# main.net
KiCad netlist of a schematic drawn in EAGLE
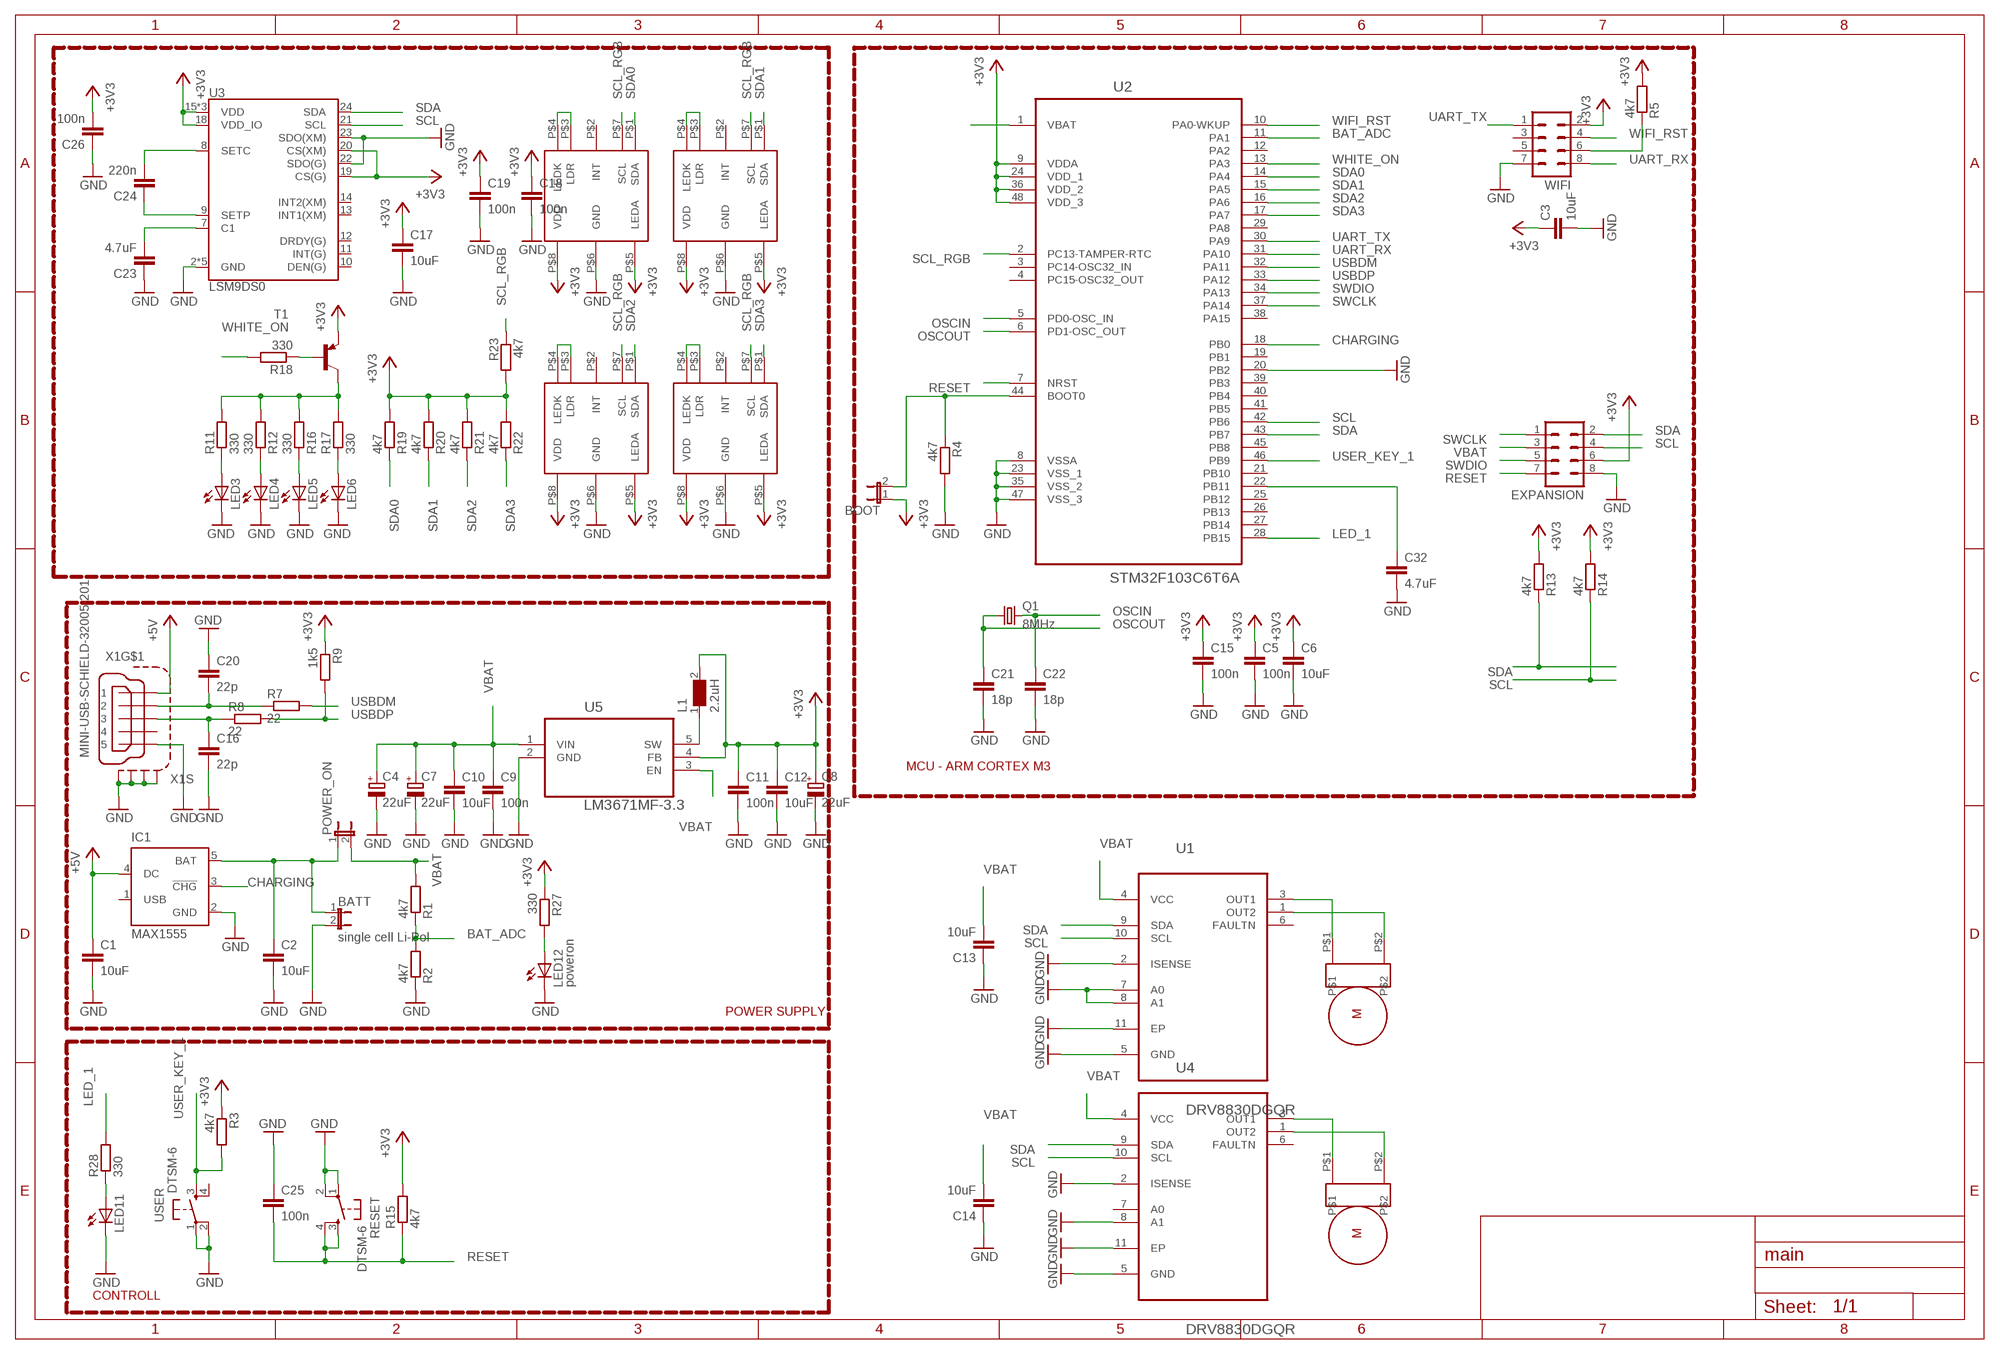
[diagram p0: schematic, sheet 1]

(export (version "E")
  (design (tool "Eeschema 10.0.6"))
  (components
    (comp (ref "BATT")
      (value "single cell Li-Pol")
      (footprint "eagle-import:JP1")
      (libsource (lib "eagle-import") (part "JP1E"))
    )
    (comp (ref "BOOT")
      (value "JP1E")
      (footprint "eagle-import:JP1")
      (libsource (lib "eagle-import") (part "JP1E"))
    )
    (comp (ref "C1")
      (value "10uF")
      (footprint "eagle-import:C0805")
      (libsource (lib "eagle-import") (part "C-EUC0805"))
    )
    (comp (ref "C2")
      (value "10uF")
      (footprint "eagle-import:C0805")
      (libsource (lib "eagle-import") (part "C-EUC0805"))
    )
    (comp (ref "C3")
      (value "10uF")
      (footprint "eagle-import:C0805")
      (libsource (lib "eagle-import") (part "C-EUC0805"))
    )
    (comp (ref "C4")
      (value "22uF")
      (footprint "eagle-import:153CLV-0505")
      (libsource (lib "eagle-import") (part "CPOL-EU153CLV-0505"))
    )
    (comp (ref "C5")
      (value "100n")
      (footprint "eagle-import:C0805")
      (libsource (lib "eagle-import") (part "C-EUC0805"))
    )
    (comp (ref "C6")
      (value "10uF")
      (footprint "eagle-import:C0805")
      (libsource (lib "eagle-import") (part "C-EUC0805"))
    )
    (comp (ref "C7")
      (value "22uF")
      (footprint "eagle-import:153CLV-0505")
      (libsource (lib "eagle-import") (part "CPOL-EU153CLV-0505"))
    )
    (comp (ref "C8")
      (value "22uF")
      (footprint "eagle-import:153CLV-0505")
      (libsource (lib "eagle-import") (part "CPOL-EU153CLV-0505"))
    )
    (comp (ref "C9")
      (value "100n")
      (footprint "eagle-import:C0805")
      (libsource (lib "eagle-import") (part "C-EUC0805"))
    )
    (comp (ref "C10")
      (value "10uF")
      (footprint "eagle-import:C0805")
      (libsource (lib "eagle-import") (part "C-EUC0805"))
    )
    (comp (ref "C11")
      (value "100n")
      (footprint "eagle-import:C0805")
      (libsource (lib "eagle-import") (part "C-EUC0805"))
    )
    (comp (ref "C12")
      (value "10uF")
      (footprint "eagle-import:C0805")
      (libsource (lib "eagle-import") (part "C-EUC0805"))
    )
    (comp (ref "C13")
      (value "10uF")
      (footprint "eagle-import:C0805")
      (libsource (lib "eagle-import") (part "C-EUC0805"))
    )
    (comp (ref "C14")
      (value "10uF")
      (footprint "eagle-import:C0805")
      (libsource (lib "eagle-import") (part "C-EUC0805"))
    )
    (comp (ref "C15")
      (value "100n")
      (footprint "eagle-import:C0805")
      (libsource (lib "eagle-import") (part "C-EUC0805"))
    )
    (comp (ref "C16")
      (value "22p")
      (footprint "eagle-import:C0805")
      (libsource (lib "eagle-import") (part "C-EUC0805"))
    )
    (comp (ref "C17")
      (value "10uF")
      (footprint "eagle-import:C0805")
      (libsource (lib "eagle-import") (part "C-EUC0805"))
    )
    (comp (ref "C18")
      (value "100n")
      (footprint "eagle-import:C0805")
      (libsource (lib "eagle-import") (part "C-EUC0805"))
    )
    (comp (ref "C19")
      (value "100n")
      (footprint "eagle-import:C0805")
      (libsource (lib "eagle-import") (part "C-EUC0805"))
    )
    (comp (ref "C20")
      (value "22p")
      (footprint "eagle-import:C0805")
      (libsource (lib "eagle-import") (part "C-EUC0805"))
    )
    (comp (ref "C21")
      (value "18p")
      (footprint "eagle-import:C0805")
      (libsource (lib "eagle-import") (part "C-EUC0805"))
    )
    (comp (ref "C22")
      (value "18p")
      (footprint "eagle-import:C0805")
      (libsource (lib "eagle-import") (part "C-EUC0805"))
    )
    (comp (ref "C23")
      (value "4.7uF")
      (footprint "eagle-import:C0805")
      (libsource (lib "eagle-import") (part "C-EUC0805"))
    )
    (comp (ref "C24")
      (value "220n")
      (footprint "eagle-import:C0805")
      (libsource (lib "eagle-import") (part "C-EUC0805"))
    )
    (comp (ref "C25")
      (value "100n")
      (footprint "eagle-import:C0805")
      (libsource (lib "eagle-import") (part "C-EUC0805"))
    )
    (comp (ref "C26")
      (value "100n")
      (footprint "eagle-import:C0805")
      (libsource (lib "eagle-import") (part "C-EUC0805"))
    )
    (comp (ref "C32")
      (value "4.7uF")
      (footprint "eagle-import:C0805")
      (libsource (lib "eagle-import") (part "C-EUC0805"))
    )
    (comp (ref "EXPANSION")
      (value "MA04-2")
      (footprint "eagle-import:MA04-2")
      (libsource (lib "eagle-import") (part "MA04-2"))
    )
    (comp (ref "IC1")
      (value "MAX1555")
      (footprint "eagle-import:SOT23-5L")
      (fields (field (name "MF") "MAXIM") (field (name "MPN") "MAX1555EZK+T"))
      (libsource (lib "eagle-import") (part "MAX1555"))
    )
    (comp (ref "L1")
      (value "2.2uH")
      (footprint "eagle-import:WE-LQ_M")
      (fields (field (name "MPN") "744032002 "))
      (libsource (lib "eagle-import") (part "WE-LQ_M-744032002"))
    )
    (comp (ref "LED3")
      (value "LEDCHIPLED_1206")
      (footprint "eagle-import:CHIPLED_1206")
      (libsource (lib "eagle-import") (part "LEDCHIPLED_1206"))
    )
    (comp (ref "LED4")
      (value "LEDCHIPLED_1206")
      (footprint "eagle-import:CHIPLED_1206")
      (libsource (lib "eagle-import") (part "LEDCHIPLED_1206"))
    )
    (comp (ref "LED5")
      (value "LEDCHIPLED_1206")
      (footprint "eagle-import:CHIPLED_1206")
      (libsource (lib "eagle-import") (part "LEDCHIPLED_1206"))
    )
    (comp (ref "LED6")
      (value "LEDCHIPLED_1206")
      (footprint "eagle-import:CHIPLED_1206")
      (libsource (lib "eagle-import") (part "LEDCHIPLED_1206"))
    )
    (comp (ref "LED11")
      (value "LEDCHIPLED_1206")
      (footprint "eagle-import:CHIPLED_1206")
      (libsource (lib "eagle-import") (part "LEDCHIPLED_1206"))
    )
    (comp (ref "LED12")
      (value "poweron")
      (footprint "eagle-import:CHIPLED_1206")
      (libsource (lib "eagle-import") (part "LEDCHIPLED_1206"))
    )
    (comp (ref "POWER_ON")
      (value "JP1E")
      (footprint "eagle-import:JP1")
      (libsource (lib "eagle-import") (part "JP1E"))
    )
    (comp (ref "Q1")
      (value "8MHz")
      (footprint "eagle-import:CTS406")
      (libsource (lib "eagle-import") (part "CRYSTALCTS406"))
    )
    (comp (ref "R1")
      (value "4k7")
      (footprint "eagle-import:M0805")
      (libsource (lib "eagle-import") (part "R-EU_M0805"))
    )
    (comp (ref "R2")
      (value "4k7")
      (footprint "eagle-import:M0805")
      (libsource (lib "eagle-import") (part "R-EU_M0805"))
    )
    (comp (ref "R3")
      (value "4k7")
      (footprint "eagle-import:M0805")
      (libsource (lib "eagle-import") (part "R-EU_M0805"))
    )
    (comp (ref "R4")
      (value "4k7")
      (footprint "eagle-import:M0805")
      (libsource (lib "eagle-import") (part "R-EU_M0805"))
    )
    (comp (ref "R5")
      (value "4k7")
      (footprint "eagle-import:M0805")
      (libsource (lib "eagle-import") (part "R-EU_M0805"))
    )
    (comp (ref "R7")
      (value "22")
      (footprint "eagle-import:M0805")
      (libsource (lib "eagle-import") (part "R-EU_M0805"))
    )
    (comp (ref "R8")
      (value "22")
      (footprint "eagle-import:M0805")
      (libsource (lib "eagle-import") (part "R-EU_M0805"))
    )
    (comp (ref "R9")
      (value "1k5")
      (footprint "eagle-import:M0805")
      (libsource (lib "eagle-import") (part "R-EU_M0805"))
    )
    (comp (ref "R11")
      (value "330")
      (footprint "eagle-import:M0805")
      (libsource (lib "eagle-import") (part "R-EU_M0805"))
    )
    (comp (ref "R12")
      (value "330")
      (footprint "eagle-import:M0805")
      (libsource (lib "eagle-import") (part "R-EU_M0805"))
    )
    (comp (ref "R13")
      (value "4k7")
      (footprint "eagle-import:M0805")
      (libsource (lib "eagle-import") (part "R-EU_M0805"))
    )
    (comp (ref "R14")
      (value "4k7")
      (footprint "eagle-import:M0805")
      (libsource (lib "eagle-import") (part "R-EU_M0805"))
    )
    (comp (ref "R15")
      (value "4k7")
      (footprint "eagle-import:M0805")
      (libsource (lib "eagle-import") (part "R-EU_M0805"))
    )
    (comp (ref "R16")
      (value "330")
      (footprint "eagle-import:M0805")
      (libsource (lib "eagle-import") (part "R-EU_M0805"))
    )
    (comp (ref "R17")
      (value "330")
      (footprint "eagle-import:M0805")
      (libsource (lib "eagle-import") (part "R-EU_M0805"))
    )
    (comp (ref "R18")
      (value "330")
      (footprint "eagle-import:M0805")
      (libsource (lib "eagle-import") (part "R-EU_M0805"))
    )
    (comp (ref "R19")
      (value "4k7")
      (footprint "eagle-import:M0805")
      (libsource (lib "eagle-import") (part "R-EU_M0805"))
    )
    (comp (ref "R20")
      (value "4k7")
      (footprint "eagle-import:M0805")
      (libsource (lib "eagle-import") (part "R-EU_M0805"))
    )
    (comp (ref "R21")
      (value "4k7")
      (footprint "eagle-import:M0805")
      (libsource (lib "eagle-import") (part "R-EU_M0805"))
    )
    (comp (ref "R22")
      (value "4k7")
      (footprint "eagle-import:M0805")
      (libsource (lib "eagle-import") (part "R-EU_M0805"))
    )
    (comp (ref "R23")
      (value "4k7")
      (footprint "eagle-import:M0805")
      (libsource (lib "eagle-import") (part "R-EU_M0805"))
    )
    (comp (ref "R27")
      (value "330")
      (footprint "eagle-import:M0805")
      (libsource (lib "eagle-import") (part "R-EU_M0805"))
    )
    (comp (ref "R28")
      (value "330")
      (footprint "eagle-import:M0805")
      (libsource (lib "eagle-import") (part "R-EU_M0805"))
    )
    (comp (ref "RESET")
      (value "DTSM-6")
      (footprint "eagle-import:DTSM-6")
      (libsource (lib "eagle-import") (part "DTSM-6"))
    )
    (comp (ref "T1")
      (value "BC857A-PNP-SOT23-BEC")
      (footprint "eagle-import:SOT23-BEC")
      (libsource (lib "eagle-import") (part "-PNP-SOT23-BECBC857A"))
    )
    (comp (ref "U$1")
      (value "APDS9950")
      (footprint "eagle-import:APDS9950")
      (libsource (lib "eagle-import") (part "APDS9950"))
    )
    (comp (ref "U$2")
      (value "APDS9950")
      (footprint "eagle-import:APDS9950")
      (libsource (lib "eagle-import") (part "APDS9950"))
    )
    (comp (ref "U$3")
      (value "APDS9950")
      (footprint "eagle-import:APDS9950")
      (libsource (lib "eagle-import") (part "APDS9950"))
    )
    (comp (ref "U$4")
      (value "APDS9950")
      (footprint "eagle-import:APDS9950")
      (libsource (lib "eagle-import") (part "APDS9950"))
    )
    (comp (ref "U$5")
      (value "MICRO_METAL_GEAR_MOTOR")
      (footprint "eagle-import:MICRO_METAL_GEAR_MOTOR")
      (libsource (lib "eagle-import") (part "MICRO_METAL_GEAR_MOTOR"))
    )
    (comp (ref "U$6")
      (value "MICRO_METAL_GEAR_MOTOR")
      (footprint "eagle-import:MICRO_METAL_GEAR_MOTOR")
      (libsource (lib "eagle-import") (part "MICRO_METAL_GEAR_MOTOR"))
    )
    (comp (ref "U1")
      (value "DRV8830DGQR")
      (footprint "eagle-import:SOP65P640X110-15N")
      (libsource (lib "eagle-import") (part "DRV8830DGQR"))
    )
    (comp (ref "U2")
      (value "STM32F103C6T6A")
      (footprint "eagle-import:QFP50P900X900X160-48N")
      (libsource (lib "eagle-import") (part "STM32F103C6T6A"))
    )
    (comp (ref "U3")
      (value "LSM9DS0")
      (footprint "eagle-import:LGA-24")
      (libsource (lib "eagle-import") (part "LSM9DS0"))
    )
    (comp (ref "U4")
      (value "DRV8830DGQR")
      (footprint "eagle-import:SOP65P640X110-15N")
      (libsource (lib "eagle-import") (part "DRV8830DGQR"))
    )
    (comp (ref "U5")
      (value "LM3671MF-3.3")
      (footprint "eagle-import:SOT95P284X122-5N")
      (libsource (lib "eagle-import") (part "LM3671MF-3.3"))
    )
    (comp (ref "USER")
      (value "DTSM-6")
      (footprint "eagle-import:DTSM-6")
      (libsource (lib "eagle-import") (part "DTSM-6"))
    )
    (comp (ref "WIFI")
      (value "MA04-2")
      (footprint "eagle-import:MA04-2")
      (libsource (lib "eagle-import") (part "MA04-2"))
    )
    (comp (ref "X1")
      (value "MINI-USB-SCHIELD-32005-201")
      (footprint "eagle-import:32005-201")
      (libsource (lib "eagle-import") (part "MINI-USB-SCHIELD-32005-201"))
    )
  )
  (nets
    (net (code "1") (name "+3V3") (class "Default")
      (node (ref "BOOT") (pin "1") (pinfunction "1_1") (pintype "passive"))
      (node (ref "C11") (pin "1") (pinfunction "1_1") (pintype "passive"))
      (node (ref "C12") (pin "1") (pinfunction "1_1") (pintype "passive"))
      (node (ref "C15") (pin "1") (pinfunction "1_1") (pintype "passive"))
      (node (ref "C17") (pin "1") (pinfunction "1_1") (pintype "passive"))
      (node (ref "C18") (pin "1") (pinfunction "1_1") (pintype "passive"))
      (node (ref "C19") (pin "1") (pinfunction "1_1") (pintype "passive"))
      (node (ref "C26") (pin "2") (pinfunction "2_2") (pintype "passive"))
      (node (ref "C3") (pin "1") (pinfunction "1_1") (pintype "passive"))
      (node (ref "C5") (pin "1") (pinfunction "1_1") (pintype "passive"))
      (node (ref "C6") (pin "1") (pinfunction "1_1") (pintype "passive"))
      (node (ref "C8") (pin "+") (pinfunction "+_+") (pintype "passive"))
      (node (ref "EXPANSION") (pin "6") (pinfunction "6_6") (pintype "passive"))
      (node (ref "L1") (pin "2") (pinfunction "2_2") (pintype "passive"))
      (node (ref "R13") (pin "2") (pinfunction "2_2") (pintype "passive"))
      (node (ref "R14") (pin "2") (pinfunction "2_2") (pintype "passive"))
      (node (ref "R15") (pin "2") (pinfunction "2_2") (pintype "passive"))
      (node (ref "R19") (pin "2") (pinfunction "2_2") (pintype "passive"))
      (node (ref "R20") (pin "2") (pinfunction "2_2") (pintype "passive"))
      (node (ref "R21") (pin "2") (pinfunction "2_2") (pintype "passive"))
      (node (ref "R22") (pin "2") (pinfunction "2_2") (pintype "passive"))
      (node (ref "R23") (pin "2") (pinfunction "2_2") (pintype "passive"))
      (node (ref "R27") (pin "1") (pinfunction "1_1") (pintype "passive"))
      (node (ref "R3") (pin "1") (pinfunction "1_1") (pintype "passive"))
      (node (ref "R5") (pin "2") (pinfunction "2_2") (pintype "passive"))
      (node (ref "R9") (pin "1") (pinfunction "1_1") (pintype "passive"))
      (node (ref "T1") (pin "E") (pinfunction "E_E") (pintype "passive"))
      (node (ref "U$1") (pin "P$5") (pinfunction "LEDA_P$5") (pintype "bidirectional"))
      (node (ref "U$1") (pin "P$8") (pinfunction "VDD_P$8") (pintype "bidirectional"))
      (node (ref "U$2") (pin "P$5") (pinfunction "LEDA_P$5") (pintype "bidirectional"))
      (node (ref "U$2") (pin "P$8") (pinfunction "VDD_P$8") (pintype "bidirectional"))
      (node (ref "U$3") (pin "P$5") (pinfunction "LEDA_P$5") (pintype "bidirectional"))
      (node (ref "U$3") (pin "P$8") (pinfunction "VDD_P$8") (pintype "bidirectional"))
      (node (ref "U$4") (pin "P$5") (pinfunction "LEDA_P$5") (pintype "bidirectional"))
      (node (ref "U$4") (pin "P$8") (pinfunction "VDD_P$8") (pintype "bidirectional"))
      (node (ref "U2") (pin "24") (pinfunction "VDD_1_24") (pintype "power_in"))
      (node (ref "U2") (pin "36") (pinfunction "VDD_2_36") (pintype "power_in"))
      (node (ref "U2") (pin "48") (pinfunction "VDD_3_48") (pintype "power_in"))
      (node (ref "U2") (pin "9") (pinfunction "VDDA_9") (pintype "power_in"))
      (node (ref "U3") (pin "15") (pinfunction "VDD_15") (pintype "bidirectional"))
      (node (ref "U3") (pin "16") (pinfunction "VDD_16") (pintype "bidirectional"))
      (node (ref "U3") (pin "17") (pinfunction "VDD_17") (pintype "bidirectional"))
      (node (ref "U3") (pin "18") (pinfunction "VDD_IO_18") (pintype "bidirectional"))
      (node (ref "U3") (pin "19") (pinfunction "CS(G)_19") (pintype "bidirectional"))
      (node (ref "U3") (pin "20") (pinfunction "CS(XM)_20") (pintype "bidirectional"))
      (node (ref "U5") (pin "4") (pinfunction "FB_4") (pintype "passive"))
      (node (ref "WIFI") (pin "2") (pinfunction "2_2") (pintype "passive"))
    )
    (net (code "2") (name "+5V") (class "Default")
      (node (ref "C1") (pin "1") (pinfunction "1_1") (pintype "passive"))
      (node (ref "IC1") (pin "4") (pinfunction "DC_4") (pintype "input"))
      (node (ref "X1") (pin "1") (pinfunction "1_1") (pintype "passive"))
    )
    (net (code "3") (name "/BAT_ADC") (class "Default")
      (node (ref "R1") (pin "1") (pinfunction "1_1") (pintype "passive"))
      (node (ref "R2") (pin "2") (pinfunction "2_2") (pintype "passive"))
      (node (ref "U2") (pin "11") (pinfunction "PA1_11") (pintype "bidirectional"))
    )
    (net (code "4") (name "/CHARGING") (class "Default")
      (node (ref "IC1") (pin "3") (pinfunction "~{CHG}_3") (pintype "output"))
      (node (ref "U2") (pin "18") (pinfunction "PB0_18") (pintype "bidirectional"))
    )
    (net (code "5") (name "/LED_1") (class "Default")
      (node (ref "R28") (pin "2") (pinfunction "2_2") (pintype "passive"))
      (node (ref "U2") (pin "28") (pinfunction "PB15_28") (pintype "bidirectional"))
    )
    (net (code "6") (name "/OSCIN") (class "Default")
      (node (ref "C22") (pin "1") (pinfunction "1_1") (pintype "passive"))
      (node (ref "Q1") (pin "3") (pinfunction "2_3") (pintype "passive"))
      (node (ref "U2") (pin "5") (pinfunction "PD0-OSC_IN_5") (pintype "bidirectional"))
    )
    (net (code "7") (name "/OSCOUT") (class "Default")
      (node (ref "C21") (pin "1") (pinfunction "1_1") (pintype "passive"))
      (node (ref "Q1") (pin "1") (pinfunction "1_1") (pintype "passive"))
      (node (ref "U2") (pin "6") (pinfunction "PD1-OSC_OUT_6") (pintype "bidirectional"))
    )
    (net (code "8") (name "/RESET") (class "Default")
      (node (ref "C25") (pin "2") (pinfunction "2_2") (pintype "passive"))
      (node (ref "EXPANSION") (pin "7") (pinfunction "7_7") (pintype "passive"))
      (node (ref "R15") (pin "1") (pinfunction "1_1") (pintype "passive"))
      (node (ref "RESET") (pin "3") (pinfunction "3_3") (pintype "passive"))
      (node (ref "RESET") (pin "4") (pinfunction "4_4") (pintype "passive"))
      (node (ref "U2") (pin "7") (pinfunction "NRST_7") (pintype "bidirectional"))
    )
    (net (code "9") (name "/SCL") (class "Default")
      (node (ref "EXPANSION") (pin "4") (pinfunction "4_4") (pintype "passive"))
      (node (ref "R14") (pin "1") (pinfunction "1_1") (pintype "passive"))
      (node (ref "U1") (pin "10") (pinfunction "SCL_10") (pintype "input"))
      (node (ref "U2") (pin "42") (pinfunction "PB6_42") (pintype "bidirectional"))
      (node (ref "U3") (pin "21") (pinfunction "SCL_21") (pintype "bidirectional"))
      (node (ref "U4") (pin "10") (pinfunction "SCL_10") (pintype "input"))
    )
    (net (code "10") (name "/SCL_RGB") (class "Default")
      (node (ref "R23") (pin "1") (pinfunction "1_1") (pintype "passive"))
      (node (ref "U$1") (pin "P$7") (pinfunction "SCL_P$7") (pintype "bidirectional"))
      (node (ref "U$2") (pin "P$7") (pinfunction "SCL_P$7") (pintype "bidirectional"))
      (node (ref "U$3") (pin "P$7") (pinfunction "SCL_P$7") (pintype "bidirectional"))
      (node (ref "U$4") (pin "P$7") (pinfunction "SCL_P$7") (pintype "bidirectional"))
      (node (ref "U2") (pin "2") (pinfunction "PC13-TAMPER-RTC_2") (pintype "bidirectional"))
    )
    (net (code "11") (name "/SDA") (class "Default")
      (node (ref "EXPANSION") (pin "2") (pinfunction "2_2") (pintype "passive"))
      (node (ref "R13") (pin "1") (pinfunction "1_1") (pintype "passive"))
      (node (ref "U1") (pin "9") (pinfunction "SDA_9") (pintype "bidirectional"))
      (node (ref "U2") (pin "43") (pinfunction "PB7_43") (pintype "bidirectional"))
      (node (ref "U3") (pin "24") (pinfunction "SDA_24") (pintype "bidirectional"))
      (node (ref "U4") (pin "9") (pinfunction "SDA_9") (pintype "bidirectional"))
    )
    (net (code "12") (name "/SDA0") (class "Default")
      (node (ref "R19") (pin "1") (pinfunction "1_1") (pintype "passive"))
      (node (ref "U$1") (pin "P$1") (pinfunction "SDA_P$1") (pintype "bidirectional"))
      (node (ref "U2") (pin "14") (pinfunction "PA4_14") (pintype "bidirectional"))
    )
    (net (code "13") (name "/SDA1") (class "Default")
      (node (ref "R20") (pin "1") (pinfunction "1_1") (pintype "passive"))
      (node (ref "U$2") (pin "P$1") (pinfunction "SDA_P$1") (pintype "bidirectional"))
      (node (ref "U2") (pin "15") (pinfunction "PA5_15") (pintype "bidirectional"))
    )
    (net (code "14") (name "/SDA2") (class "Default")
      (node (ref "R21") (pin "1") (pinfunction "1_1") (pintype "passive"))
      (node (ref "U$3") (pin "P$1") (pinfunction "SDA_P$1") (pintype "bidirectional"))
      (node (ref "U2") (pin "16") (pinfunction "PA6_16") (pintype "bidirectional"))
    )
    (net (code "15") (name "/SDA3") (class "Default")
      (node (ref "R22") (pin "1") (pinfunction "1_1") (pintype "passive"))
      (node (ref "U$4") (pin "P$1") (pinfunction "SDA_P$1") (pintype "bidirectional"))
      (node (ref "U2") (pin "17") (pinfunction "PA7_17") (pintype "bidirectional"))
    )
    (net (code "16") (name "/SWCLK") (class "Default")
      (node (ref "EXPANSION") (pin "1") (pinfunction "1_1") (pintype "passive"))
      (node (ref "U2") (pin "37") (pinfunction "PA14_37") (pintype "bidirectional"))
    )
    (net (code "17") (name "/SWDIO") (class "Default")
      (node (ref "EXPANSION") (pin "5") (pinfunction "5_5") (pintype "passive"))
      (node (ref "U2") (pin "34") (pinfunction "PA13_34") (pintype "bidirectional"))
    )
    (net (code "18") (name "/UART_RX") (class "Default")
      (node (ref "U2") (pin "31") (pinfunction "PA10_31") (pintype "bidirectional"))
      (node (ref "WIFI") (pin "8") (pinfunction "8_8") (pintype "passive"))
    )
    (net (code "19") (name "/UART_TX") (class "Default")
      (node (ref "U2") (pin "30") (pinfunction "PA9_30") (pintype "bidirectional"))
      (node (ref "WIFI") (pin "1") (pinfunction "1_1") (pintype "passive"))
    )
    (net (code "20") (name "/USBDM") (class "Default")
      (node (ref "R7") (pin "2") (pinfunction "2_2") (pintype "passive"))
      (node (ref "U2") (pin "32") (pinfunction "PA11_32") (pintype "bidirectional"))
    )
    (net (code "21") (name "/USBDP") (class "Default")
      (node (ref "R8") (pin "2") (pinfunction "2_2") (pintype "passive"))
      (node (ref "R9") (pin "2") (pinfunction "2_2") (pintype "passive"))
      (node (ref "U2") (pin "33") (pinfunction "PA12_33") (pintype "bidirectional"))
    )
    (net (code "22") (name "/USER_KEY_1") (class "Default")
      (node (ref "R3") (pin "2") (pinfunction "2_2") (pintype "passive"))
      (node (ref "U2") (pin "46") (pinfunction "PB9_46") (pintype "bidirectional"))
      (node (ref "USER") (pin "3") (pinfunction "3_3") (pintype "passive"))
    )
    (net (code "23") (name "/VBAT") (class "Default")
      (node (ref "C10") (pin "1") (pinfunction "1_1") (pintype "passive"))
      (node (ref "C13") (pin "2") (pinfunction "2_2") (pintype "passive"))
      (node (ref "C14") (pin "2") (pinfunction "2_2") (pintype "passive"))
      (node (ref "C4") (pin "+") (pinfunction "+_+") (pintype "passive"))
      (node (ref "C7") (pin "+") (pinfunction "+_+") (pintype "passive"))
      (node (ref "C9") (pin "1") (pinfunction "1_1") (pintype "passive"))
      (node (ref "EXPANSION") (pin "3") (pinfunction "3_3") (pintype "passive"))
      (node (ref "POWER_ON") (pin "2") (pinfunction "2_2") (pintype "passive"))
      (node (ref "R1") (pin "2") (pinfunction "2_2") (pintype "passive"))
      (node (ref "U1") (pin "4") (pinfunction "VCC_4") (pintype "power_in"))
      (node (ref "U4") (pin "4") (pinfunction "VCC_4") (pintype "power_in"))
      (node (ref "U5") (pin "1") (pinfunction "VIN_1") (pintype "input"))
      (node (ref "U5") (pin "3") (pinfunction "EN_3") (pintype "passive"))
    )
    (net (code "24") (name "/WHITE_ON") (class "Default")
      (node (ref "R18") (pin "2") (pinfunction "2_2") (pintype "passive"))
      (node (ref "U2") (pin "13") (pinfunction "PA3_13") (pintype "bidirectional"))
    )
    (net (code "25") (name "/WIFI_RST") (class "Default")
      (node (ref "U2") (pin "10") (pinfunction "PA0-WKUP_10") (pintype "bidirectional"))
      (node (ref "WIFI") (pin "4") (pinfunction "4_4") (pintype "passive"))
    )
    (net (code "26") (name "GND") (class "Default")
      (node (ref "BATT") (pin "2") (pinfunction "2_2") (pintype "passive"))
      (node (ref "C1") (pin "2") (pinfunction "2_2") (pintype "passive"))
      (node (ref "C10") (pin "2") (pinfunction "2_2") (pintype "passive"))
      (node (ref "C11") (pin "2") (pinfunction "2_2") (pintype "passive"))
      (node (ref "C12") (pin "2") (pinfunction "2_2") (pintype "passive"))
      (node (ref "C13") (pin "1") (pinfunction "1_1") (pintype "passive"))
      (node (ref "C14") (pin "1") (pinfunction "1_1") (pintype "passive"))
      (node (ref "C15") (pin "2") (pinfunction "2_2") (pintype "passive"))
      (node (ref "C16") (pin "2") (pinfunction "2_2") (pintype "passive"))
      (node (ref "C17") (pin "2") (pinfunction "2_2") (pintype "passive"))
      (node (ref "C18") (pin "2") (pinfunction "2_2") (pintype "passive"))
      (node (ref "C19") (pin "2") (pinfunction "2_2") (pintype "passive"))
      (node (ref "C2") (pin "2") (pinfunction "2_2") (pintype "passive"))
      (node (ref "C20") (pin "1") (pinfunction "1_1") (pintype "passive"))
      (node (ref "C21") (pin "2") (pinfunction "2_2") (pintype "passive"))
      (node (ref "C22") (pin "2") (pinfunction "2_2") (pintype "passive"))
      (node (ref "C23") (pin "1") (pinfunction "1_1") (pintype "passive"))
      (node (ref "C25") (pin "1") (pinfunction "1_1") (pintype "passive"))
      (node (ref "C26") (pin "1") (pinfunction "1_1") (pintype "passive"))
      (node (ref "C3") (pin "2") (pinfunction "2_2") (pintype "passive"))
      (node (ref "C32") (pin "2") (pinfunction "2_2") (pintype "passive"))
      (node (ref "C4") (pin "-") (pinfunction "-_-") (pintype "passive"))
      (node (ref "C5") (pin "2") (pinfunction "2_2") (pintype "passive"))
      (node (ref "C6") (pin "2") (pinfunction "2_2") (pintype "passive"))
      (node (ref "C7") (pin "-") (pinfunction "-_-") (pintype "passive"))
      (node (ref "C8") (pin "-") (pinfunction "-_-") (pintype "passive"))
      (node (ref "C9") (pin "2") (pinfunction "2_2") (pintype "passive"))
      (node (ref "EXPANSION") (pin "8") (pinfunction "8_8") (pintype "passive"))
      (node (ref "IC1") (pin "2") (pinfunction "GND_2") (pintype "power_in"))
      (node (ref "LED11") (pin "C") (pinfunction "C_C") (pintype "passive"))
      (node (ref "LED12") (pin "C") (pinfunction "C_C") (pintype "passive"))
      (node (ref "LED3") (pin "C") (pinfunction "C_C") (pintype "passive"))
      (node (ref "LED4") (pin "C") (pinfunction "C_C") (pintype "passive"))
      (node (ref "LED5") (pin "C") (pinfunction "C_C") (pintype "passive"))
      (node (ref "LED6") (pin "C") (pinfunction "C_C") (pintype "passive"))
      (node (ref "R2") (pin "1") (pinfunction "1_1") (pintype "passive"))
      (node (ref "R4") (pin "2") (pinfunction "2_2") (pintype "passive"))
      (node (ref "RESET") (pin "1") (pinfunction "1_1") (pintype "passive"))
      (node (ref "RESET") (pin "2") (pinfunction "2_2") (pintype "passive"))
      (node (ref "U$1") (pin "P$6") (pinfunction "GND_P$6") (pintype "bidirectional"))
      (node (ref "U$2") (pin "P$6") (pinfunction "GND_P$6") (pintype "bidirectional"))
      (node (ref "U$3") (pin "P$6") (pinfunction "GND_P$6") (pintype "bidirectional"))
      (node (ref "U$4") (pin "P$6") (pinfunction "GND_P$6") (pintype "bidirectional"))
      (node (ref "U1") (pin "11") (pinfunction "EP_11") (pintype "passive"))
      (node (ref "U1") (pin "2") (pinfunction "ISENSE_2") (pintype "input"))
      (node (ref "U1") (pin "5") (pinfunction "GND_5") (pintype "passive"))
      (node (ref "U1") (pin "7") (pinfunction "A0_7") (pintype "input"))
      (node (ref "U1") (pin "8") (pinfunction "A1_8") (pintype "input"))
      (node (ref "U2") (pin "20") (pinfunction "PB2_20") (pintype "bidirectional"))
      (node (ref "U2") (pin "23") (pinfunction "VSS_1_23") (pintype "passive"))
      (node (ref "U2") (pin "35") (pinfunction "VSS_2_35") (pintype "passive"))
      (node (ref "U2") (pin "47") (pinfunction "VSS_3_47") (pintype "passive"))
      (node (ref "U2") (pin "8") (pinfunction "VSSA_8") (pintype "passive"))
      (node (ref "U3") (pin "2") (pinfunction "GND_2") (pintype "bidirectional"))
      (node (ref "U3") (pin "22") (pinfunction "SDO(G)_22") (pintype "bidirectional"))
      (node (ref "U3") (pin "23") (pinfunction "SDO(XM)_23") (pintype "bidirectional"))
      (node (ref "U3") (pin "3") (pinfunction "GND_3") (pintype "bidirectional"))
      (node (ref "U3") (pin "4") (pinfunction "GND_4") (pintype "bidirectional"))
      (node (ref "U3") (pin "5") (pinfunction "GND_5") (pintype "bidirectional"))
      (node (ref "U3") (pin "6") (pinfunction "GND_6") (pintype "bidirectional"))
      (node (ref "U4") (pin "11") (pinfunction "EP_11") (pintype "passive"))
      (node (ref "U4") (pin "2") (pinfunction "ISENSE_2") (pintype "input"))
      (node (ref "U4") (pin "5") (pinfunction "GND_5") (pintype "passive"))
      (node (ref "U4") (pin "8") (pinfunction "A1_8") (pintype "input"))
      (node (ref "U5") (pin "2") (pinfunction "GND_2") (pintype "passive"))
      (node (ref "USER") (pin "1") (pinfunction "1_1") (pintype "passive"))
      (node (ref "USER") (pin "2") (pinfunction "2_2") (pintype "passive"))
      (node (ref "WIFI") (pin "7") (pinfunction "7_7") (pintype "passive"))
      (node (ref "X1") (pin "5") (pinfunction "5_5") (pintype "passive"))
      (node (ref "X1") (pin "M1") (pinfunction "S1_M1") (pintype "passive"))
      (node (ref "X1") (pin "M2") (pinfunction "S2_M2") (pintype "passive"))
      (node (ref "X1") (pin "M3") (pinfunction "S3_M3") (pintype "passive"))
      (node (ref "X1") (pin "M4") (pinfunction "S4_M4") (pintype "passive"))
    )
    (net (code "27") (name "Net-(C16-Pad1)") (class "Default")
      (node (ref "C16") (pin "1") (pinfunction "1_1") (pintype "passive"))
      (node (ref "R8") (pin "1") (pinfunction "1_1") (pintype "passive"))
      (node (ref "X1") (pin "3") (pinfunction "3_3") (pintype "passive"))
    )
    (net (code "28") (name "Net-(C20-Pad2)") (class "Default")
      (node (ref "C20") (pin "2") (pinfunction "2_2") (pintype "passive"))
      (node (ref "R7") (pin "1") (pinfunction "1_1") (pintype "passive"))
      (node (ref "X1") (pin "2") (pinfunction "2_2") (pintype "passive"))
    )
    (net (code "29") (name "Net-(IC1-BAT)") (class "Default")
      (node (ref "BATT") (pin "1") (pinfunction "1_1") (pintype "passive"))
      (node (ref "C2") (pin "1") (pinfunction "1_1") (pintype "passive"))
      (node (ref "IC1") (pin "5") (pinfunction "BAT_5") (pintype "passive"))
      (node (ref "POWER_ON") (pin "1") (pinfunction "1_1") (pintype "passive"))
    )
    (net (code "30") (name "Net-(LED3-PadA)") (class "Default")
      (node (ref "LED3") (pin "A") (pinfunction "A_A") (pintype "passive"))
      (node (ref "R11") (pin "1") (pinfunction "1_1") (pintype "passive"))
    )
    (net (code "31") (name "Net-(LED4-PadA)") (class "Default")
      (node (ref "LED4") (pin "A") (pinfunction "A_A") (pintype "passive"))
      (node (ref "R12") (pin "1") (pinfunction "1_1") (pintype "passive"))
    )
    (net (code "32") (name "Net-(LED5-PadA)") (class "Default")
      (node (ref "LED5") (pin "A") (pinfunction "A_A") (pintype "passive"))
      (node (ref "R16") (pin "1") (pinfunction "1_1") (pintype "passive"))
    )
    (net (code "33") (name "Net-(LED6-PadA)") (class "Default")
      (node (ref "LED6") (pin "A") (pinfunction "A_A") (pintype "passive"))
      (node (ref "R17") (pin "1") (pinfunction "1_1") (pintype "passive"))
    )
    (net (code "34") (name "Net-(LED11-PadA)") (class "Default")
      (node (ref "LED11") (pin "A") (pinfunction "A_A") (pintype "passive"))
      (node (ref "R28") (pin "1") (pinfunction "1_1") (pintype "passive"))
    )
    (net (code "35") (name "Net-(LED12-PadA)") (class "Default")
      (node (ref "LED12") (pin "A") (pinfunction "A_A") (pintype "passive"))
      (node (ref "R27") (pin "2") (pinfunction "2_2") (pintype "passive"))
    )
    (net (code "36") (name "Net-(R5-Pad1)") (class "Default")
      (node (ref "R5") (pin "1") (pinfunction "1_1") (pintype "passive"))
      (node (ref "WIFI") (pin "6") (pinfunction "6_6") (pintype "passive"))
    )
    (net (code "37") (name "Net-(R11-Pad2)") (class "Default")
      (node (ref "R11") (pin "2") (pinfunction "2_2") (pintype "passive"))
      (node (ref "R12") (pin "2") (pinfunction "2_2") (pintype "passive"))
      (node (ref "R16") (pin "2") (pinfunction "2_2") (pintype "passive"))
      (node (ref "R17") (pin "2") (pinfunction "2_2") (pintype "passive"))
      (node (ref "T1") (pin "C") (pinfunction "C_C") (pintype "passive"))
    )
    (net (code "38") (name "Net-(R18-Pad1)") (class "Default")
      (node (ref "R18") (pin "1") (pinfunction "1_1") (pintype "passive"))
      (node (ref "T1") (pin "B") (pinfunction "B_B") (pintype "passive"))
    )
    (net (code "39") (name "Net-(U$1-LDR)") (class "Default")
      (node (ref "U$1") (pin "P$3") (pinfunction "LDR_P$3") (pintype "bidirectional"))
      (node (ref "U$1") (pin "P$4") (pinfunction "LEDK_P$4") (pintype "bidirectional"))
    )
    (net (code "40") (name "Net-(U$2-LDR)") (class "Default")
      (node (ref "U$2") (pin "P$3") (pinfunction "LDR_P$3") (pintype "bidirectional"))
      (node (ref "U$2") (pin "P$4") (pinfunction "LEDK_P$4") (pintype "bidirectional"))
    )
    (net (code "41") (name "Net-(U$3-LDR)") (class "Default")
      (node (ref "U$3") (pin "P$3") (pinfunction "LDR_P$3") (pintype "bidirectional"))
      (node (ref "U$3") (pin "P$4") (pinfunction "LEDK_P$4") (pintype "bidirectional"))
    )
    (net (code "42") (name "Net-(U$4-LDR)") (class "Default")
      (node (ref "U$4") (pin "P$3") (pinfunction "LDR_P$3") (pintype "bidirectional"))
      (node (ref "U$4") (pin "P$4") (pinfunction "LEDK_P$4") (pintype "bidirectional"))
    )
    (net (code "43") (name "Net-(U1-OUT1)") (class "Default")
      (node (ref "U$5") (pin "P$1") (pinfunction "P$1_P$1") (pintype "bidirectional"))
      (node (ref "U1") (pin "3") (pinfunction "OUT1_3") (pintype "output"))
    )
    (net (code "44") (name "Net-(U1-OUT2)") (class "Default")
      (node (ref "U$5") (pin "P$2") (pinfunction "P$2_P$2") (pintype "bidirectional"))
      (node (ref "U1") (pin "1") (pinfunction "OUT2_1") (pintype "output"))
    )
    (net (code "45") (name "Net-(U2-BOOT0)") (class "Default")
      (node (ref "BOOT") (pin "2") (pinfunction "2_2") (pintype "passive"))
      (node (ref "R4") (pin "1") (pinfunction "1_1") (pintype "passive"))
      (node (ref "U2") (pin "44") (pinfunction "BOOT0_44") (pintype "input"))
    )
    (net (code "46") (name "Net-(U2-PB11)") (class "Default")
      (node (ref "C32") (pin "1") (pinfunction "1_1") (pintype "passive"))
      (node (ref "U2") (pin "22") (pinfunction "PB11_22") (pintype "bidirectional"))
    )
    (net (code "47") (name "Net-(U3-C1)") (class "Default")
      (node (ref "C23") (pin "2") (pinfunction "2_2") (pintype "passive"))
      (node (ref "U3") (pin "7") (pinfunction "C1_7") (pintype "bidirectional"))
    )
    (net (code "48") (name "Net-(U3-SETC)") (class "Default")
      (node (ref "C24") (pin "2") (pinfunction "2_2") (pintype "passive"))
      (node (ref "U3") (pin "8") (pinfunction "SETC_8") (pintype "bidirectional"))
    )
    (net (code "49") (name "Net-(U3-SETP)") (class "Default")
      (node (ref "C24") (pin "1") (pinfunction "1_1") (pintype "passive"))
      (node (ref "U3") (pin "9") (pinfunction "SETP_9") (pintype "bidirectional"))
    )
    (net (code "50") (name "Net-(U4-OUT1)") (class "Default")
      (node (ref "U$6") (pin "P$1") (pinfunction "P$1_P$1") (pintype "bidirectional"))
      (node (ref "U4") (pin "3") (pinfunction "OUT1_3") (pintype "output"))
    )
    (net (code "51") (name "Net-(U4-OUT2)") (class "Default")
      (node (ref "U$6") (pin "P$2") (pinfunction "P$2_P$2") (pintype "bidirectional"))
      (node (ref "U4") (pin "1") (pinfunction "OUT2_1") (pintype "output"))
    )
    (net (code "52") (name "Net-(U5-SW)") (class "Default")
      (node (ref "L1") (pin "1") (pinfunction "1_1") (pintype "passive"))
      (node (ref "U5") (pin "5") (pinfunction "SW_5") (pintype "output"))
    )
    (net (code "53") (name "unconnected-(IC1-USB-Pad1)") (class "Default")
      (node (ref "IC1") (pin "1") (pinfunction "USB_1") (pintype "input"))
    )
    (net (code "54") (name "unconnected-(U$1-INT-PadP$2)") (class "Default")
      (node (ref "U$1") (pin "P$2") (pinfunction "INT_P$2") (pintype "bidirectional"))
    )
    (net (code "55") (name "unconnected-(U$2-INT-PadP$2)") (class "Default")
      (node (ref "U$2") (pin "P$2") (pinfunction "INT_P$2") (pintype "bidirectional"))
    )
    (net (code "56") (name "unconnected-(U$3-INT-PadP$2)") (class "Default")
      (node (ref "U$3") (pin "P$2") (pinfunction "INT_P$2") (pintype "bidirectional"))
    )
    (net (code "57") (name "unconnected-(U$4-INT-PadP$2)") (class "Default")
      (node (ref "U$4") (pin "P$2") (pinfunction "INT_P$2") (pintype "bidirectional"))
    )
    (net (code "58") (name "unconnected-(U1-FAULTN-Pad6)") (class "Default")
      (node (ref "U1") (pin "6") (pinfunction "FAULTN_6") (pintype "output"))
    )
    (net (code "59") (name "unconnected-(U2-PA2-Pad12)") (class "Default")
      (node (ref "U2") (pin "12") (pinfunction "PA2_12") (pintype "bidirectional"))
    )
    (net (code "60") (name "unconnected-(U2-PA8-Pad29)") (class "Default")
      (node (ref "U2") (pin "29") (pinfunction "PA8_29") (pintype "bidirectional"))
    )
    (net (code "61") (name "unconnected-(U2-PA15-Pad38)") (class "Default")
      (node (ref "U2") (pin "38") (pinfunction "PA15_38") (pintype "bidirectional"))
    )
    (net (code "62") (name "unconnected-(U2-PB1-Pad19)") (class "Default")
      (node (ref "U2") (pin "19") (pinfunction "PB1_19") (pintype "bidirectional"))
    )
    (net (code "63") (name "unconnected-(U2-PB3-Pad39)") (class "Default")
      (node (ref "U2") (pin "39") (pinfunction "PB3_39") (pintype "bidirectional"))
    )
    (net (code "64") (name "unconnected-(U2-PB4-Pad40)") (class "Default")
      (node (ref "U2") (pin "40") (pinfunction "PB4_40") (pintype "bidirectional"))
    )
    (net (code "65") (name "unconnected-(U2-PB5-Pad41)") (class "Default")
      (node (ref "U2") (pin "41") (pinfunction "PB5_41") (pintype "bidirectional"))
    )
    (net (code "66") (name "unconnected-(U2-PB8-Pad45)") (class "Default")
      (node (ref "U2") (pin "45") (pinfunction "PB8_45") (pintype "bidirectional"))
    )
    (net (code "67") (name "unconnected-(U2-PB10-Pad21)") (class "Default")
      (node (ref "U2") (pin "21") (pinfunction "PB10_21") (pintype "bidirectional"))
    )
    (net (code "68") (name "unconnected-(U2-PB12-Pad25)") (class "Default")
      (node (ref "U2") (pin "25") (pinfunction "PB12_25") (pintype "bidirectional"))
    )
    (net (code "69") (name "unconnected-(U2-PB13-Pad26)") (class "Default")
      (node (ref "U2") (pin "26") (pinfunction "PB13_26") (pintype "bidirectional"))
    )
    (net (code "70") (name "unconnected-(U2-PB14-Pad27)") (class "Default")
      (node (ref "U2") (pin "27") (pinfunction "PB14_27") (pintype "bidirectional"))
    )
    (net (code "71") (name "unconnected-(U2-PC14-OSC32_IN-Pad3)") (class "Default")
      (node (ref "U2") (pin "3") (pinfunction "PC14-OSC32_IN_3") (pintype "bidirectional"))
    )
    (net (code "72") (name "unconnected-(U2-PC15-OSC32_OUT-Pad4)") (class "Default")
      (node (ref "U2") (pin "4") (pinfunction "PC15-OSC32_OUT_4") (pintype "bidirectional"))
    )
    (net (code "73") (name "unconnected-(U2-VBAT-Pad1)") (class "Default")
      (node (ref "U2") (pin "1") (pinfunction "VBAT_1") (pintype "power_in"))
    )
    (net (code "74") (name "unconnected-(U3-DEN(G)-Pad10)") (class "Default")
      (node (ref "U3") (pin "10") (pinfunction "DEN(G)_10") (pintype "bidirectional"))
    )
    (net (code "75") (name "unconnected-(U3-DRDY(G)-Pad12)") (class "Default")
      (node (ref "U3") (pin "12") (pinfunction "DRDY(G)_12") (pintype "bidirectional"))
    )
    (net (code "76") (name "unconnected-(U3-INT(G)-Pad11)") (class "Default")
      (node (ref "U3") (pin "11") (pinfunction "INT(G)_11") (pintype "bidirectional"))
    )
    (net (code "77") (name "unconnected-(U3-INT1(XM)-Pad13)") (class "Default")
      (node (ref "U3") (pin "13") (pinfunction "INT1(XM)_13") (pintype "bidirectional"))
    )
    (net (code "78") (name "unconnected-(U3-INT2(XM)-Pad14)") (class "Default")
      (node (ref "U3") (pin "14") (pinfunction "INT2(XM)_14") (pintype "bidirectional"))
    )
    (net (code "79") (name "unconnected-(U4-A0-Pad7)") (class "Default")
      (node (ref "U4") (pin "7") (pinfunction "A0_7") (pintype "input"))
    )
    (net (code "80") (name "unconnected-(U4-FAULTN-Pad6)") (class "Default")
      (node (ref "U4") (pin "6") (pinfunction "FAULTN_6") (pintype "output"))
    )
    (net (code "81") (name "unconnected-(USER-Pad4)") (class "Default")
      (node (ref "USER") (pin "4") (pinfunction "4_4") (pintype "passive"))
    )
    (net (code "82") (name "unconnected-(WIFI-Pad3)") (class "Default")
      (node (ref "WIFI") (pin "3") (pinfunction "3_3") (pintype "passive"))
    )
    (net (code "83") (name "unconnected-(WIFI-Pad5)") (class "Default")
      (node (ref "WIFI") (pin "5") (pinfunction "5_5") (pintype "passive"))
    )
    (net (code "84") (name "unconnected-(X1-Pad4)") (class "Default")
      (node (ref "X1") (pin "4") (pinfunction "4_4") (pintype "passive"))
    )
  )
)
